# Sheet1.net
KiCad netlist of a schematic drawn in Altium Designer
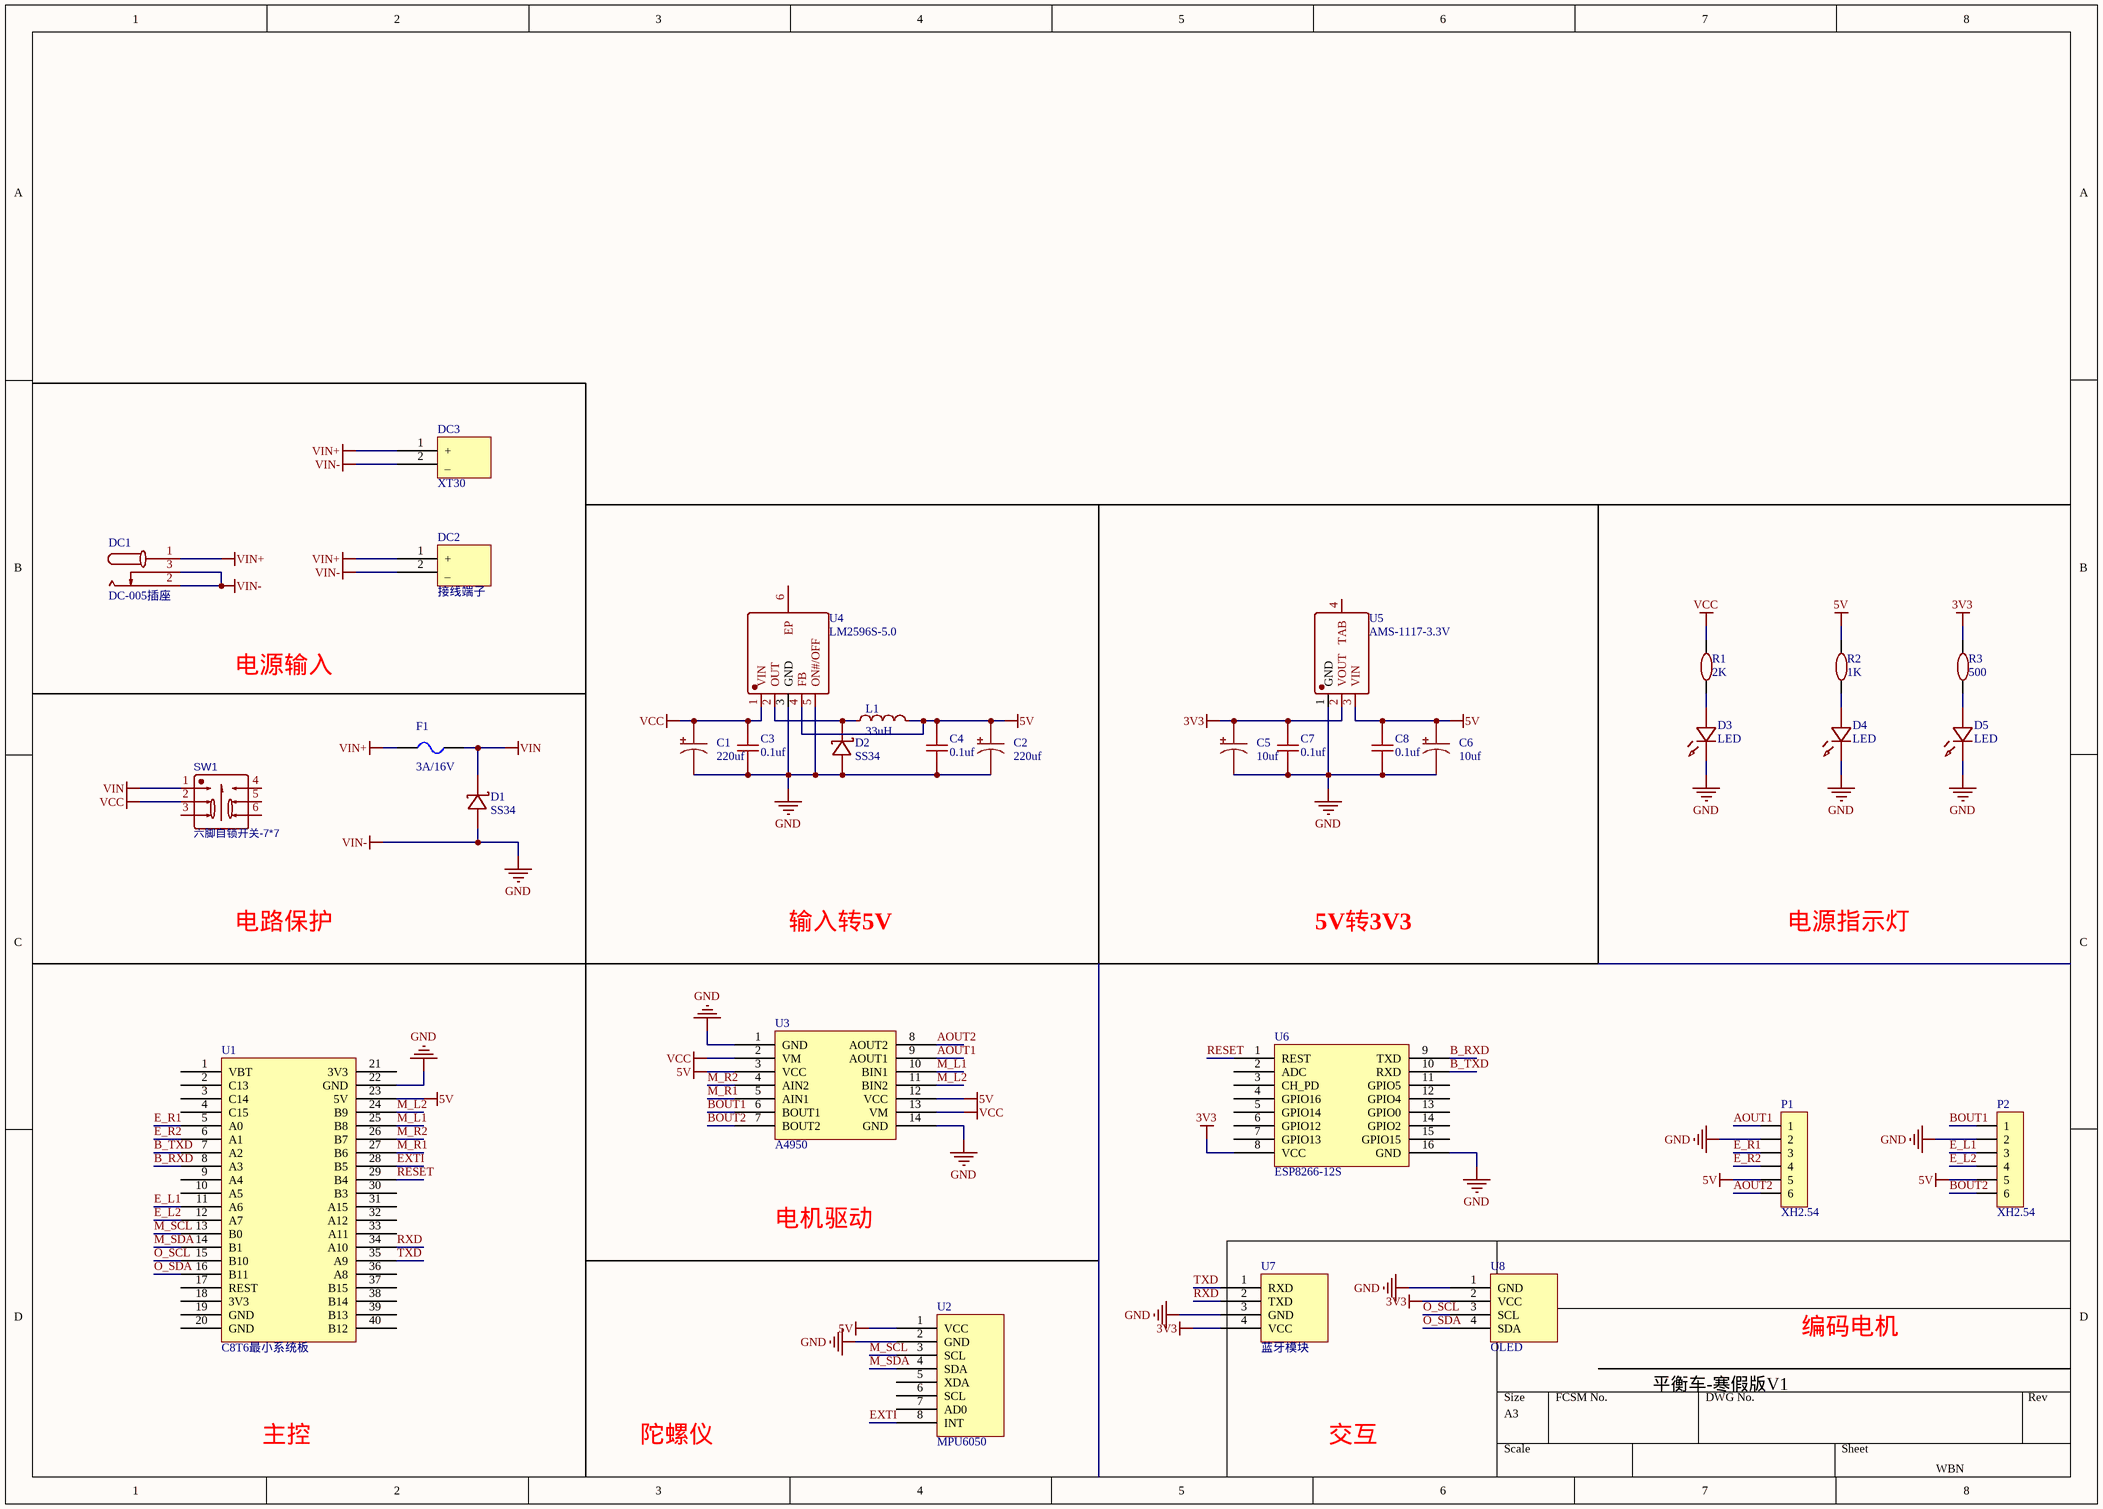
[diagram p0: Sheet1.SchDoc]

(export (version "E")
  (design (tool "Eeschema 10.0.6"))
  (components
    (comp (ref "C1")
      (value "220uf")
      (footprint "CAP 2.5*6.3*11.2")
      (description "25V/220uf")
      (libsource (lib "RCLD") (part "C_6*11"))
    )
    (comp (ref "C2")
      (value "220uf")
      (footprint "CAP 2.5*6.3*11.2")
      (description "25V/220uf")
      (libsource (lib "RCLD") (part "C_6*11"))
    )
    (comp (ref "C3")
      (value "0.1uf")
      (footprint "C_0603")
      (description "4.7nf-4.7uf")
      (libsource (lib "RCLD") (part "C_0603"))
    )
    (comp (ref "C4")
      (value "0.1uf")
      (footprint "C_0603")
      (description "4.7nf-4.7uf")
      (libsource (lib "RCLD") (part "C_0603"))
    )
    (comp (ref "C5")
      (value "10uf")
      (footprint "CD A(3216)")
      (description "16V/10uf")
      (libsource (lib "RCLD") (part "C_A型钽电容"))
    )
    (comp (ref "C6")
      (value "10uf")
      (footprint "CD A(3216)")
      (description "16V/10uf")
      (libsource (lib "RCLD") (part "C_A型钽电容"))
    )
    (comp (ref "C7")
      (value "0.1uf")
      (footprint "C_0603")
      (description "4.7nf-4.7uf")
      (libsource (lib "RCLD") (part "C_0603"))
    )
    (comp (ref "C8")
      (value "0.1uf")
      (footprint "C_0603")
      (description "4.7nf-4.7uf")
      (libsource (lib "RCLD") (part "C_0603"))
    )
    (comp (ref "D1")
      (value "SS34")
      (footprint "D_1N5819")
      (description "3A/40")
      (libsource (lib "RCLD") (part "SS34"))
    )
    (comp (ref "D2")
      (value "SS34")
      (footprint "D_1N5819")
      (description "3A/40")
      (libsource (lib "RCLD") (part "SS34"))
    )
    (comp (ref "D3") (value "LED") (footprint "LED_0603") (libsource (lib "RCLD") (part "LED_0603")))
    (comp (ref "D4") (value "LED") (footprint "LED_0603") (libsource (lib "RCLD") (part "LED_0603")))
    (comp (ref "D5") (value "LED") (footprint "LED_0603") (libsource (lib "RCLD") (part "LED_0603")))
    (comp (ref "DC1")
      (value "DC-005插座")
      (footprint "DC-005-5.5*2.1")
      (libsource (lib "电源接口") (part "DC-005插座"))
    )
    (comp (ref "DC2") (value "接线端子") (footprint "接线端子") (libsource (lib "电源接口") (part "接线端子")))
    (comp (ref "DC3") (value "XT30") (footprint "XT30-M") (libsource (lib "电源接口") (part "XT30")))
    (comp (ref "F1")
      (value "3A/16V")
      (footprint "FU 1812")
      (fields (field (name "版权归属") "封装库来自淘宝卖家 ID：黄晶宝石"))
      (libsource (lib "RCLD") (part "FU"))
    )
    (comp (ref "L1")
      (value "33uH")
      (footprint "L_SWPA4020")
      (description "1.5uH-33uH")
      (libsource (lib "RCLD") (part "L_33uH_4020"))
    )
    (comp (ref "P1") (value "XH2.54") (footprint "XH2.54-LI-6P") (libsource (lib "XH2.54") (part "XH2.54")))
    (comp (ref "P2") (value "XH2.54") (footprint "XH2.54-LI-6P") (libsource (lib "XH2.54") (part "XH2.54")))
    (comp (ref "R1") (value "2K") (footprint "R_0603") (libsource (lib "RCLD") (part "R_0603")))
    (comp (ref "R2") (value "1K") (footprint "R_0603") (libsource (lib "RCLD") (part "R_0603")))
    (comp (ref "R3") (value "500") (footprint "R_0603") (libsource (lib "RCLD") (part "R_0603")))
    (comp (ref "SW1")
      (value "六脚自锁开关-7*7")
      (footprint "KFT DIP-7X7")
      (fields
        (field (name "BOM_SUPPLIER PART") "C318862")
        (field (name "BOM_MANUFACTURER PART") "XKB7070-Z-92")
        (field (name "CONTRIBUTOR") "LCSC")
      )
      (libsource (lib "按键开关") (part "六脚自锁开关-7*7"))
    )
    (comp (ref "U1") (value "C8T6最小系统板") (footprint "C8T6最小系统板") (libsource (lib "常用模块") (part "C8T6最小系统板")))
    (comp (ref "U2") (value "MPU6050") (footprint "MPU6050") (libsource (lib "常用模块") (part "MPU6050")))
    (comp (ref "U3") (value "A4950") (footprint "A4950") (libsource (lib "常用模块") (part "A4950")))
    (comp (ref "U4")
      (value "LM2596S-5.0")
      (footprint "T0263")
      (description "降压3.3V-12V")
      (libsource (lib "电源管理IC") (part "LM2596S"))
    )
    (comp (ref "U5")
      (value "AMS-1117-3.3V")
      (footprint "SOT223")
      (description "降压1.2V-5V")
      (libsource (lib "电源管理IC") (part "AMS1117"))
    )
    (comp (ref "U6")
      (value "ESP8266-12S")
      (footprint "ESP8266-12S")
      (libsource (lib "常用模块") (part "ESP8266-12S"))
    )
    (comp (ref "U7")
      (value "蓝牙模块")
      (footprint "蓝牙模块")
      (description "四线蓝牙模块")
      (libsource (lib "常用模块") (part "蓝牙模块"))
    )
    (comp (ref "U8") (value "OLED") (footprint "OLED") (libsource (lib "常用模块") (part "OLED")))
  )
  (nets
    (net (code "1") (name "/AOUT1") (class "Default")
      (node (ref "P1") (pin "1") (pinfunction "1_1") (pintype "passive"))
      (node (ref "U3") (pin "9") (pinfunction "AOUT1_9") (pintype "passive"))
    )
    (net (code "2") (name "/AOUT2") (class "Default")
      (node (ref "P1") (pin "6") (pinfunction "6_6") (pintype "passive"))
      (node (ref "U3") (pin "8") (pinfunction "AOUT2_8") (pintype "passive"))
    )
    (net (code "3") (name "/BOUT1") (class "Default")
      (node (ref "P2") (pin "1") (pinfunction "1_1") (pintype "passive"))
      (node (ref "U3") (pin "6") (pinfunction "BOUT1_6") (pintype "passive"))
    )
    (net (code "4") (name "/BOUT2") (class "Default")
      (node (ref "P2") (pin "6") (pinfunction "6_6") (pintype "passive"))
      (node (ref "U3") (pin "7") (pinfunction "BOUT2_7") (pintype "passive"))
    )
    (net (code "5") (name "/B_RXD") (class "Default")
      (node (ref "U1") (pin "8") (pinfunction "A3_8") (pintype "passive"))
      (node (ref "U6") (pin "9") (pinfunction "TXD_9") (pintype "passive"))
    )
    (net (code "6") (name "/B_TXD") (class "Default")
      (node (ref "U1") (pin "7") (pinfunction "A2_7") (pintype "passive"))
      (node (ref "U6") (pin "10") (pinfunction "RXD_10") (pintype "passive"))
    )
    (net (code "7") (name "/EXTI") (class "Default")
      (node (ref "U1") (pin "28") (pinfunction "B5_28") (pintype "passive"))
      (node (ref "U2") (pin "8") (pinfunction "INT_8") (pintype "passive"))
    )
    (net (code "8") (name "/E_L1") (class "Default")
      (node (ref "P2") (pin "3") (pinfunction "3_3") (pintype "passive"))
      (node (ref "U1") (pin "11") (pinfunction "A6_11") (pintype "passive"))
    )
    (net (code "9") (name "/E_L2") (class "Default")
      (node (ref "P2") (pin "4") (pinfunction "4_4") (pintype "passive"))
      (node (ref "U1") (pin "12") (pinfunction "A7_12") (pintype "passive"))
    )
    (net (code "10") (name "/E_R1") (class "Default")
      (node (ref "P1") (pin "3") (pinfunction "3_3") (pintype "passive"))
      (node (ref "U1") (pin "5") (pinfunction "A0_5") (pintype "passive"))
    )
    (net (code "11") (name "/E_R2") (class "Default")
      (node (ref "P1") (pin "4") (pinfunction "4_4") (pintype "passive"))
      (node (ref "U1") (pin "6") (pinfunction "A1_6") (pintype "passive"))
    )
    (net (code "12") (name "/M_L1") (class "Default")
      (node (ref "U1") (pin "25") (pinfunction "B8_25") (pintype "passive"))
      (node (ref "U3") (pin "10") (pinfunction "BIN1_10") (pintype "passive"))
    )
    (net (code "13") (name "/M_L2") (class "Default")
      (node (ref "U1") (pin "24") (pinfunction "B9_24") (pintype "passive"))
      (node (ref "U3") (pin "11") (pinfunction "BIN2_11") (pintype "passive"))
    )
    (net (code "14") (name "/M_R1") (class "Default")
      (node (ref "U1") (pin "27") (pinfunction "B6_27") (pintype "passive"))
      (node (ref "U3") (pin "5") (pinfunction "AIN1_5") (pintype "passive"))
    )
    (net (code "15") (name "/M_R2") (class "Default")
      (node (ref "U1") (pin "26") (pinfunction "B7_26") (pintype "passive"))
      (node (ref "U3") (pin "4") (pinfunction "AIN2_4") (pintype "passive"))
    )
    (net (code "16") (name "/M_SCL") (class "Default")
      (node (ref "U1") (pin "13") (pinfunction "B0_13") (pintype "passive"))
      (node (ref "U2") (pin "3") (pinfunction "SCL_3") (pintype "passive"))
    )
    (net (code "17") (name "/M_SDA") (class "Default")
      (node (ref "U1") (pin "14") (pinfunction "B1_14") (pintype "passive"))
      (node (ref "U2") (pin "4") (pinfunction "SDA_4") (pintype "passive"))
    )
    (net (code "18") (name "/O_SCL") (class "Default")
      (node (ref "U1") (pin "15") (pinfunction "B10_15") (pintype "passive"))
      (node (ref "U8") (pin "3") (pinfunction "SCL_3") (pintype "passive"))
    )
    (net (code "19") (name "/O_SDA") (class "Default")
      (node (ref "U1") (pin "16") (pinfunction "B11_16") (pintype "passive"))
      (node (ref "U8") (pin "4") (pinfunction "SDA_4") (pintype "passive"))
    )
    (net (code "20") (name "/RESET") (class "Default")
      (node (ref "U1") (pin "29") (pinfunction "B4_29") (pintype "passive"))
      (node (ref "U6") (pin "1") (pinfunction "REST_1") (pintype "passive"))
    )
    (net (code "21") (name "/RXD") (class "Default")
      (node (ref "U1") (pin "34") (pinfunction "A10_34") (pintype "passive"))
      (node (ref "U7") (pin "2") (pinfunction "TXD_2") (pintype "passive"))
    )
    (net (code "22") (name "/TXD") (class "Default")
      (node (ref "U1") (pin "35") (pinfunction "A9_35") (pintype "passive"))
      (node (ref "U7") (pin "1") (pinfunction "RXD_1") (pintype "passive"))
    )
    (net (code "23") (name "3V3") (class "Default")
      (node (ref "C5") (pin "1") (pinfunction "1_1") (pintype "passive"))
      (node (ref "C7") (pin "2") (pinfunction "2_2") (pintype "passive"))
      (node (ref "R3") (pin "2") (pinfunction "2_2") (pintype "passive"))
      (node (ref "U5") (pin "2") (pinfunction "VOUT_2") (pintype "passive"))
      (node (ref "U6") (pin "8") (pinfunction "VCC_8") (pintype "passive"))
      (node (ref "U7") (pin "4") (pinfunction "VCC_4") (pintype "passive"))
      (node (ref "U8") (pin "2") (pinfunction "VCC_2") (pintype "passive"))
    )
    (net (code "24") (name "5V") (class "Default")
      (node (ref "C2") (pin "1") (pinfunction "1_1") (pintype "passive"))
      (node (ref "C4") (pin "2") (pinfunction "2_2") (pintype "passive"))
      (node (ref "C6") (pin "1") (pinfunction "1_1") (pintype "passive"))
      (node (ref "C8") (pin "2") (pinfunction "2_2") (pintype "passive"))
      (node (ref "L1") (pin "2") (pinfunction "2_2") (pintype "passive"))
      (node (ref "P1") (pin "5") (pinfunction "5_5") (pintype "passive"))
      (node (ref "P2") (pin "5") (pinfunction "5_5") (pintype "passive"))
      (node (ref "R2") (pin "2") (pinfunction "2_2") (pintype "passive"))
      (node (ref "U1") (pin "23") (pinfunction "5V_23") (pintype "passive"))
      (node (ref "U2") (pin "1") (pinfunction "VCC_1") (pintype "passive"))
      (node (ref "U3") (pin "12") (pinfunction "VCC_12") (pintype "passive"))
      (node (ref "U3") (pin "3") (pinfunction "VCC_3") (pintype "passive"))
      (node (ref "U4") (pin "4") (pinfunction "FB_4") (pintype "passive"))
      (node (ref "U5") (pin "3") (pinfunction "VIN_3") (pintype "passive"))
    )
    (net (code "25") (name "GND") (class "Default")
      (node (ref "C1") (pin "2") (pinfunction "2_2") (pintype "passive"))
      (node (ref "C2") (pin "2") (pinfunction "2_2") (pintype "passive"))
      (node (ref "C3") (pin "1") (pinfunction "1_1") (pintype "passive"))
      (node (ref "C4") (pin "1") (pinfunction "1_1") (pintype "passive"))
      (node (ref "C5") (pin "2") (pinfunction "2_2") (pintype "passive"))
      (node (ref "C6") (pin "2") (pinfunction "2_2") (pintype "passive"))
      (node (ref "C7") (pin "1") (pinfunction "1_1") (pintype "passive"))
      (node (ref "C8") (pin "1") (pinfunction "1_1") (pintype "passive"))
      (node (ref "D1") (pin "2") (pinfunction "2_2") (pintype "passive"))
      (node (ref "D2") (pin "2") (pinfunction "2_2") (pintype "passive"))
      (node (ref "D3") (pin "1") (pinfunction "K_1") (pintype "passive"))
      (node (ref "D4") (pin "1") (pinfunction "K_1") (pintype "passive"))
      (node (ref "D5") (pin "1") (pinfunction "K_1") (pintype "passive"))
      (node (ref "DC1") (pin "2") (pinfunction "2_2") (pintype "passive"))
      (node (ref "DC1") (pin "3") (pinfunction "3_3") (pintype "passive"))
      (node (ref "DC2") (pin "2") (pinfunction "__2") (pintype "passive"))
      (node (ref "DC3") (pin "2") (pinfunction "__2") (pintype "passive"))
      (node (ref "P1") (pin "2") (pinfunction "2_2") (pintype "passive"))
      (node (ref "P2") (pin "2") (pinfunction "2_2") (pintype "passive"))
      (node (ref "U1") (pin "22") (pinfunction "GND_22") (pintype "passive"))
      (node (ref "U2") (pin "2") (pinfunction "GND_2") (pintype "passive"))
      (node (ref "U3") (pin "1") (pinfunction "GND_1") (pintype "passive"))
      (node (ref "U3") (pin "14") (pinfunction "GND_14") (pintype "passive"))
      (node (ref "U4") (pin "3") (pinfunction "GND_3") (pintype "passive"))
      (node (ref "U4") (pin "5") (pinfunction "ON#/OFF_5") (pintype "passive"))
      (node (ref "U5") (pin "1") (pinfunction "GND_1") (pintype "passive"))
      (node (ref "U6") (pin "16") (pinfunction "GND_16") (pintype "passive"))
      (node (ref "U7") (pin "3") (pinfunction "GND_3") (pintype "passive"))
      (node (ref "U8") (pin "1") (pinfunction "GND_1") (pintype "passive"))
    )
    (net (code "26") (name "Net-(D3-A)") (class "Default")
      (node (ref "D3") (pin "2") (pinfunction "A_2") (pintype "passive"))
      (node (ref "R1") (pin "1") (pinfunction "1_1") (pintype "passive"))
    )
    (net (code "27") (name "Net-(D4-A)") (class "Default")
      (node (ref "D4") (pin "2") (pinfunction "A_2") (pintype "passive"))
      (node (ref "R2") (pin "1") (pinfunction "1_1") (pintype "passive"))
    )
    (net (code "28") (name "Net-(D5-A)") (class "Default")
      (node (ref "D5") (pin "2") (pinfunction "A_2") (pintype "passive"))
      (node (ref "R3") (pin "1") (pinfunction "1_1") (pintype "passive"))
    )
    (net (code "29") (name "Net-(U4-OUT)") (class "Default")
      (node (ref "D2") (pin "1") (pinfunction "1_1") (pintype "passive"))
      (node (ref "L1") (pin "1") (pinfunction "1_1") (pintype "passive"))
      (node (ref "U4") (pin "2") (pinfunction "OUT_2") (pintype "passive"))
    )
    (net (code "30") (name "VCC") (class "Default")
      (node (ref "C1") (pin "1") (pinfunction "1_1") (pintype "passive"))
      (node (ref "C3") (pin "2") (pinfunction "2_2") (pintype "passive"))
      (node (ref "R1") (pin "2") (pinfunction "2_2") (pintype "passive"))
      (node (ref "SW1") (pin "2") (pinfunction "2_2") (pintype "passive"))
      (node (ref "U3") (pin "13") (pinfunction "VM_13") (pintype "passive"))
      (node (ref "U3") (pin "2") (pinfunction "VM_2") (pintype "passive"))
      (node (ref "U4") (pin "1") (pinfunction "VIN_1") (pintype "passive"))
    )
    (net (code "31") (name "VIN") (class "Default")
      (node (ref "D1") (pin "1") (pinfunction "1_1") (pintype "passive"))
      (node (ref "F1") (pin "2") (pinfunction "2_2") (pintype "passive"))
      (node (ref "SW1") (pin "1") (pinfunction "1_1") (pintype "passive"))
    )
    (net (code "32") (name "VIN+") (class "Default")
      (node (ref "DC1") (pin "1") (pinfunction "1_1") (pintype "passive"))
      (node (ref "DC2") (pin "1") (pinfunction "+_1") (pintype "passive"))
      (node (ref "DC3") (pin "1") (pinfunction "+_1") (pintype "passive"))
      (node (ref "F1") (pin "1") (pinfunction "1_1") (pintype "passive"))
    )
    (net (code "33") (name "unconnected-(SW1-Pad3)") (class "Default")
      (node (ref "SW1") (pin "3") (pinfunction "3_3") (pintype "passive"))
    )
    (net (code "34") (name "unconnected-(SW1-Pad4)") (class "Default")
      (node (ref "SW1") (pin "4") (pinfunction "4_4") (pintype "passive"))
    )
    (net (code "35") (name "unconnected-(SW1-Pad5)") (class "Default")
      (node (ref "SW1") (pin "5") (pinfunction "5_5") (pintype "passive"))
    )
    (net (code "36") (name "unconnected-(SW1-Pad6)") (class "Default")
      (node (ref "SW1") (pin "6") (pinfunction "6_6") (pintype "passive"))
    )
    (net (code "37") (name "unconnected-(U1-3V3-Pad18)") (class "Default")
      (node (ref "U1") (pin "18") (pinfunction "3V3_18") (pintype "passive"))
    )
    (net (code "38") (name "unconnected-(U1-3V3-Pad21)") (class "Default")
      (node (ref "U1") (pin "21") (pinfunction "3V3_21") (pintype "passive"))
    )
    (net (code "39") (name "unconnected-(U1-A4-Pad9)") (class "Default")
      (node (ref "U1") (pin "9") (pinfunction "A4_9") (pintype "passive"))
    )
    (net (code "40") (name "unconnected-(U1-A5-Pad10)") (class "Default")
      (node (ref "U1") (pin "10") (pinfunction "A5_10") (pintype "passive"))
    )
    (net (code "41") (name "unconnected-(U1-A8-Pad36)") (class "Default")
      (node (ref "U1") (pin "36") (pinfunction "A8_36") (pintype "passive"))
    )
    (net (code "42") (name "unconnected-(U1-A11-Pad33)") (class "Default")
      (node (ref "U1") (pin "33") (pinfunction "A11_33") (pintype "passive"))
    )
    (net (code "43") (name "unconnected-(U1-A12-Pad32)") (class "Default")
      (node (ref "U1") (pin "32") (pinfunction "A12_32") (pintype "passive"))
    )
    (net (code "44") (name "unconnected-(U1-A15-Pad31)") (class "Default")
      (node (ref "U1") (pin "31") (pinfunction "A15_31") (pintype "passive"))
    )
    (net (code "45") (name "unconnected-(U1-B3-Pad30)") (class "Default")
      (node (ref "U1") (pin "30") (pinfunction "B3_30") (pintype "passive"))
    )
    (net (code "46") (name "unconnected-(U1-B12-Pad40)") (class "Default")
      (node (ref "U1") (pin "40") (pinfunction "B12_40") (pintype "passive"))
    )
    (net (code "47") (name "unconnected-(U1-B13-Pad39)") (class "Default")
      (node (ref "U1") (pin "39") (pinfunction "B13_39") (pintype "passive"))
    )
    (net (code "48") (name "unconnected-(U1-B14-Pad38)") (class "Default")
      (node (ref "U1") (pin "38") (pinfunction "B14_38") (pintype "passive"))
    )
    (net (code "49") (name "unconnected-(U1-B15-Pad37)") (class "Default")
      (node (ref "U1") (pin "37") (pinfunction "B15_37") (pintype "passive"))
    )
    (net (code "50") (name "unconnected-(U1-C13-Pad2)") (class "Default")
      (node (ref "U1") (pin "2") (pinfunction "C13_2") (pintype "passive"))
    )
    (net (code "51") (name "unconnected-(U1-C14-Pad3)") (class "Default")
      (node (ref "U1") (pin "3") (pinfunction "C14_3") (pintype "passive"))
    )
    (net (code "52") (name "unconnected-(U1-C15-Pad4)") (class "Default")
      (node (ref "U1") (pin "4") (pinfunction "C15_4") (pintype "passive"))
    )
    (net (code "53") (name "unconnected-(U1-GND-Pad19)") (class "Default")
      (node (ref "U1") (pin "19") (pinfunction "GND_19") (pintype "passive"))
    )
    (net (code "54") (name "unconnected-(U1-GND-Pad20)") (class "Default")
      (node (ref "U1") (pin "20") (pinfunction "GND_20") (pintype "passive"))
    )
    (net (code "55") (name "unconnected-(U1-REST-Pad17)") (class "Default")
      (node (ref "U1") (pin "17") (pinfunction "REST_17") (pintype "passive"))
    )
    (net (code "56") (name "unconnected-(U1-VBT-Pad1)") (class "Default")
      (node (ref "U1") (pin "1") (pinfunction "VBT_1") (pintype "passive"))
    )
    (net (code "57") (name "unconnected-(U2-AD0-Pad7)") (class "Default")
      (node (ref "U2") (pin "7") (pinfunction "AD0_7") (pintype "passive"))
    )
    (net (code "58") (name "unconnected-(U2-SCL-Pad6)") (class "Default")
      (node (ref "U2") (pin "6") (pinfunction "SCL_6") (pintype "passive"))
    )
    (net (code "59") (name "unconnected-(U2-XDA-Pad5)") (class "Default")
      (node (ref "U2") (pin "5") (pinfunction "XDA_5") (pintype "passive"))
    )
    (net (code "60") (name "unconnected-(U4-EP-Pad6)") (class "Default")
      (node (ref "U4") (pin "6") (pinfunction "EP_6") (pintype "passive"))
    )
    (net (code "61") (name "unconnected-(U5-TAB-Pad4)") (class "Default")
      (node (ref "U5") (pin "4") (pinfunction "TAB_4") (pintype "passive"))
    )
    (net (code "62") (name "unconnected-(U6-ADC-Pad2)") (class "Default")
      (node (ref "U6") (pin "2") (pinfunction "ADC_2") (pintype "passive"))
    )
    (net (code "63") (name "unconnected-(U6-CH_PD-Pad3)") (class "Default")
      (node (ref "U6") (pin "3") (pinfunction "CH_PD_3") (pintype "passive"))
    )
    (net (code "64") (name "unconnected-(U6-GPIO0-Pad13)") (class "Default")
      (node (ref "U6") (pin "13") (pinfunction "GPIO0_13") (pintype "passive"))
    )
    (net (code "65") (name "unconnected-(U6-GPIO2-Pad14)") (class "Default")
      (node (ref "U6") (pin "14") (pinfunction "GPIO2_14") (pintype "passive"))
    )
    (net (code "66") (name "unconnected-(U6-GPIO4-Pad12)") (class "Default")
      (node (ref "U6") (pin "12") (pinfunction "GPIO4_12") (pintype "passive"))
    )
    (net (code "67") (name "unconnected-(U6-GPIO5-Pad11)") (class "Default")
      (node (ref "U6") (pin "11") (pinfunction "GPIO5_11") (pintype "passive"))
    )
    (net (code "68") (name "unconnected-(U6-GPIO12-Pad6)") (class "Default")
      (node (ref "U6") (pin "6") (pinfunction "GPIO12_6") (pintype "passive"))
    )
    (net (code "69") (name "unconnected-(U6-GPIO13-Pad7)") (class "Default")
      (node (ref "U6") (pin "7") (pinfunction "GPIO13_7") (pintype "passive"))
    )
    (net (code "70") (name "unconnected-(U6-GPIO14-Pad5)") (class "Default")
      (node (ref "U6") (pin "5") (pinfunction "GPIO14_5") (pintype "passive"))
    )
    (net (code "71") (name "unconnected-(U6-GPIO15-Pad15)") (class "Default")
      (node (ref "U6") (pin "15") (pinfunction "GPIO15_15") (pintype "passive"))
    )
    (net (code "72") (name "unconnected-(U6-GPIO16-Pad4)") (class "Default")
      (node (ref "U6") (pin "4") (pinfunction "GPIO16_4") (pintype "passive"))
    )
  )
)
